# AC.net
KiCad netlist of a schematic drawn in EAGLE
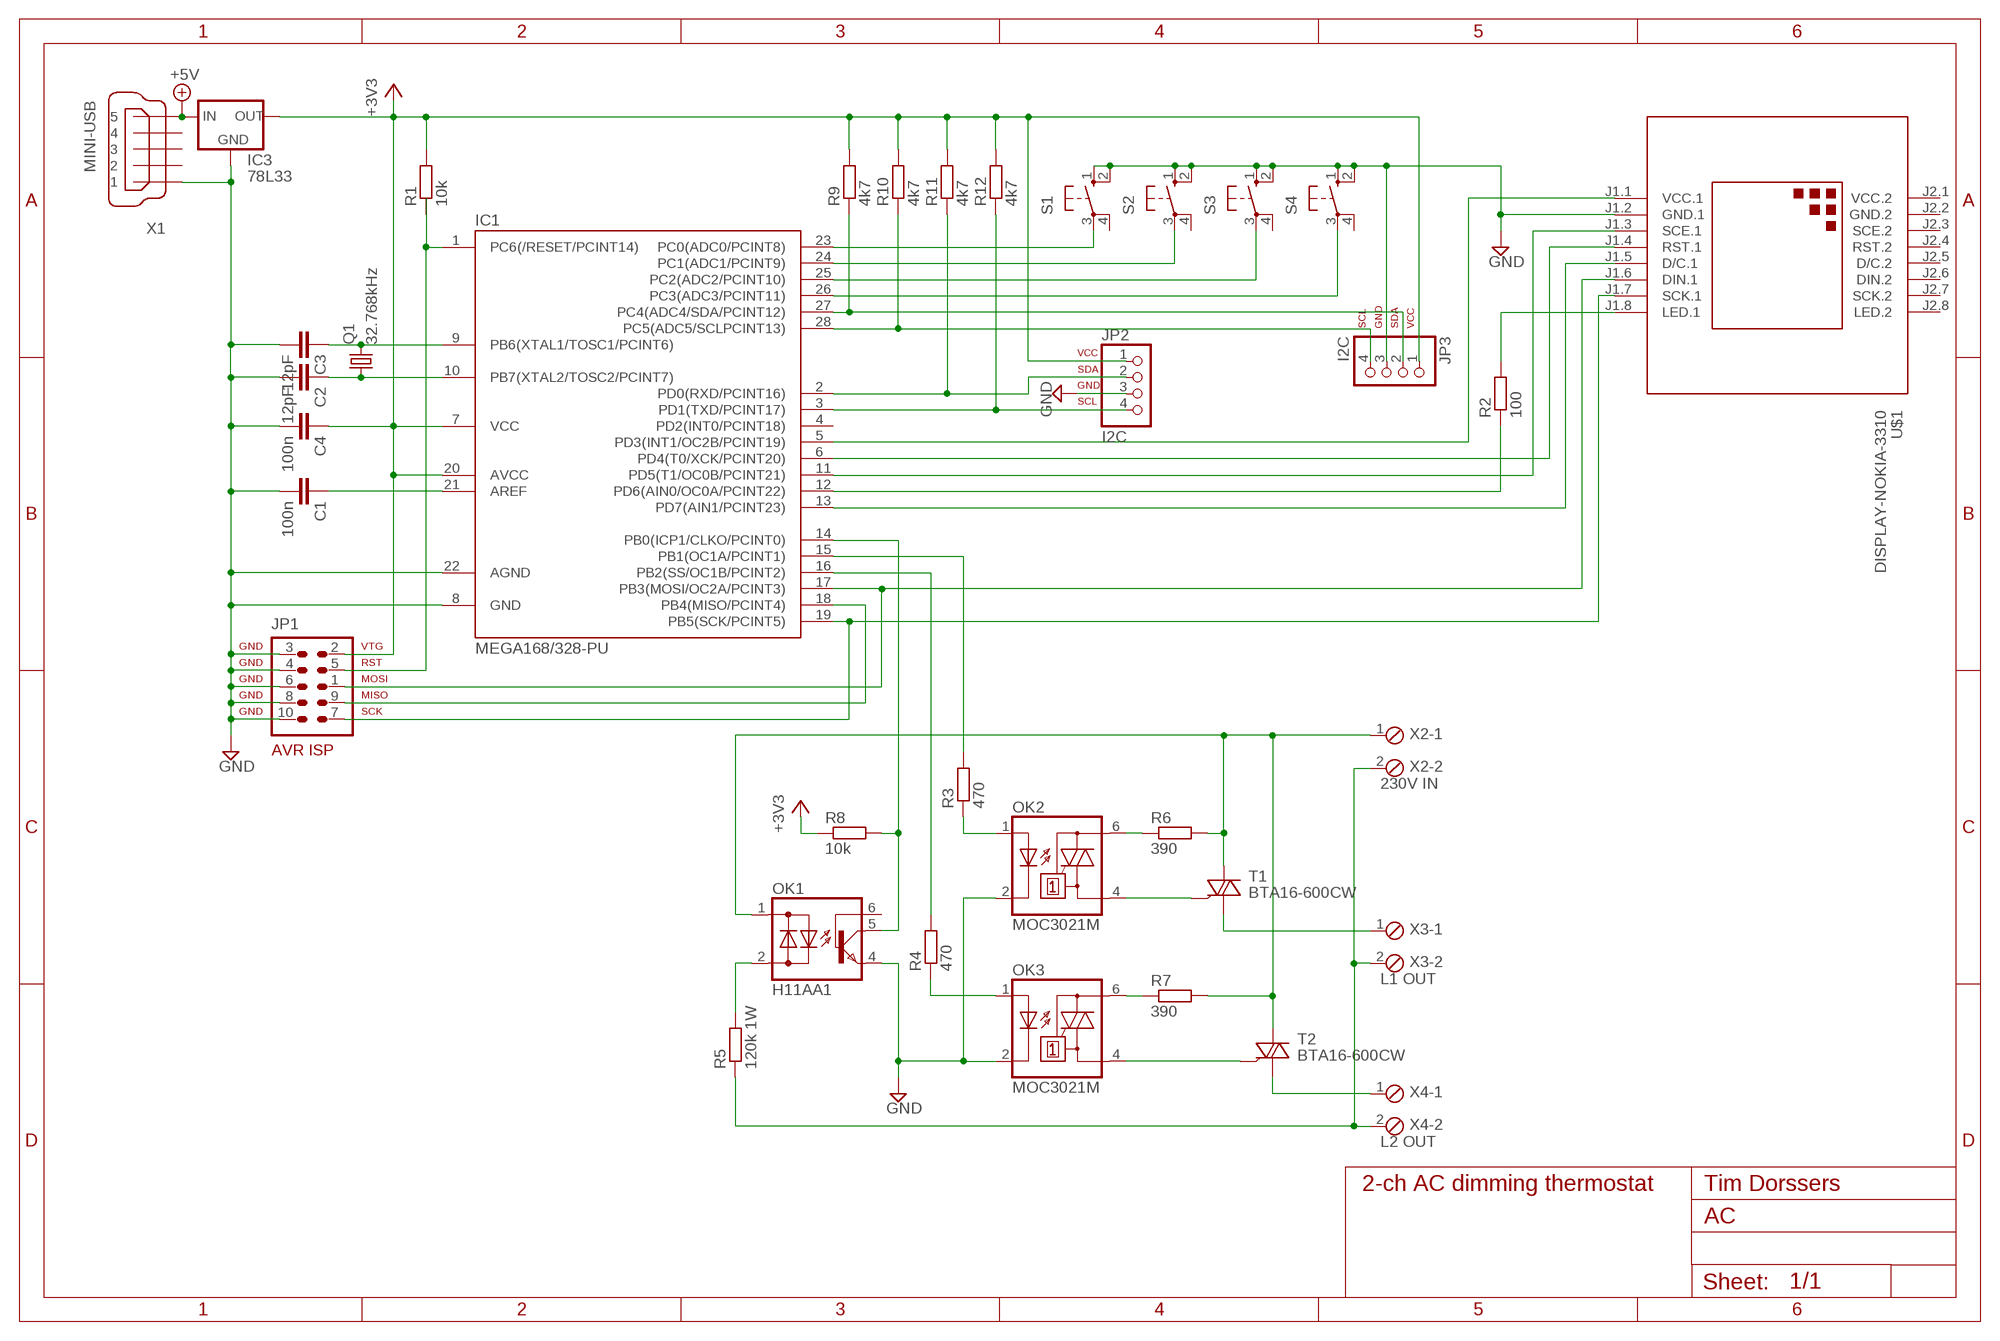
[diagram p0: schematic, sheet 1]

(export (version "E")
  (design (tool "Eeschema 10.0.6"))
  (components
    (comp (ref "C1")
      (value "100n")
      (footprint "eagle-import:C025-025X050")
      (libsource (lib "eagle-import") (part "C-EU025-025X050"))
    )
    (comp (ref "C2")
      (value "12pF")
      (footprint "eagle-import:C025-024X044")
      (libsource (lib "eagle-import") (part "C-EU025-024X044"))
    )
    (comp (ref "C3")
      (value "12pF")
      (footprint "eagle-import:C025-024X044")
      (libsource (lib "eagle-import") (part "C-EU025-024X044"))
    )
    (comp (ref "C4")
      (value "100n")
      (footprint "eagle-import:C025-025X050")
      (libsource (lib "eagle-import") (part "C-EU025-025X050"))
    )
    (comp (ref "IC1")
      (value "MEGA168/328-PU")
      (footprint "eagle-import:DIL28-3")
      (libsource (lib "eagle-import") (part "MEGA48/88/168-PU"))
    )
    (comp (ref "IC3")
      (value "78L33")
      (footprint "eagle-import:78LXX")
      (libsource (lib "eagle-import") (part "78LXX"))
    )
    (comp (ref "JP1")
      (value "AVR-ISP-10")
      (footprint "eagle-import:AVR-ISP-10")
      (libsource (lib "eagle-import") (part "AVR-ISP-10"))
    )
    (comp (ref "JP2")
      (value "I2C")
      (footprint "eagle-import:1X04")
      (libsource (lib "eagle-import") (part "PINHD-1X4"))
    )
    (comp (ref "JP3")
      (value "I2C")
      (footprint "eagle-import:1X04")
      (libsource (lib "eagle-import") (part "PINHD-1X4"))
    )
    (comp (ref "OK1")
      (value "H11AA1")
      (footprint "eagle-import:DIL06")
      (fields (field (name "MF") "VISHAY/TELEFUNKEN") (field (name "MPN") "IL250"))
      (libsource (lib "eagle-import") (part "IL250"))
    )
    (comp (ref "OK2")
      (value "MOC3021M")
      (footprint "eagle-import:DIL06")
      (fields (field (name "MF") "FAIRCHILD SEMICONDUCTOR") (field (name "MPN") "MOC3021-M"))
      (libsource (lib "eagle-import") (part "MOC30M21"))
    )
    (comp (ref "OK3")
      (value "MOC3021M")
      (footprint "eagle-import:DIL06")
      (fields (field (name "MF") "FAIRCHILD SEMICONDUCTOR") (field (name "MPN") "MOC3021-M"))
      (libsource (lib "eagle-import") (part "MOC30M21"))
    )
    (comp (ref "Q1")
      (value "32.768kHz")
      (footprint "eagle-import:HC49U-V")
      (libsource (lib "eagle-import") (part "CRYSTALHC49U-V"))
    )
    (comp (ref "R1")
      (value "10k")
      (footprint "eagle-import:0204_7")
      (libsource (lib "eagle-import") (part "R-EU_0204/7"))
    )
    (comp (ref "R2")
      (value "100")
      (footprint "eagle-import:0204_7")
      (libsource (lib "eagle-import") (part "R-EU_0204/7"))
    )
    (comp (ref "R3")
      (value "470")
      (footprint "eagle-import:0204_7")
      (libsource (lib "eagle-import") (part "R-EU_0204/7"))
    )
    (comp (ref "R4")
      (value "470")
      (footprint "eagle-import:0204_7")
      (libsource (lib "eagle-import") (part "R-EU_0204/7"))
    )
    (comp (ref "R5")
      (value "120k 1W")
      (footprint "eagle-import:0207_10")
      (libsource (lib "eagle-import") (part "R-EU_0207/10"))
    )
    (comp (ref "R6")
      (value "390")
      (footprint "eagle-import:0204_7")
      (libsource (lib "eagle-import") (part "R-EU_0204/7"))
    )
    (comp (ref "R7")
      (value "390")
      (footprint "eagle-import:0204_7")
      (libsource (lib "eagle-import") (part "R-EU_0204/7"))
    )
    (comp (ref "R8")
      (value "10k")
      (footprint "eagle-import:0207_10")
      (libsource (lib "eagle-import") (part "R-EU_0207/10"))
    )
    (comp (ref "R9")
      (value "4k7")
      (footprint "eagle-import:0204_7")
      (libsource (lib "eagle-import") (part "R-EU_0204/7"))
    )
    (comp (ref "R10")
      (value "4k7")
      (footprint "eagle-import:0204_7")
      (libsource (lib "eagle-import") (part "R-EU_0204/7"))
    )
    (comp (ref "R11")
      (value "4k7")
      (footprint "eagle-import:0204_7")
      (libsource (lib "eagle-import") (part "R-EU_0204/7"))
    )
    (comp (ref "R12")
      (value "4k7")
      (footprint "eagle-import:0204_7")
      (libsource (lib "eagle-import") (part "R-EU_0204/7"))
    )
    (comp (ref "S1")
      (value "10-XX")
      (footprint "eagle-import:B3F-10XX")
      (fields (field (name "MPN") "B3F-1000"))
      (libsource (lib "eagle-import") (part "10-XX"))
    )
    (comp (ref "S2")
      (value "10-XX")
      (footprint "eagle-import:B3F-10XX")
      (fields (field (name "MPN") "B3F-1000"))
      (libsource (lib "eagle-import") (part "10-XX"))
    )
    (comp (ref "S3")
      (value "10-XX")
      (footprint "eagle-import:B3F-10XX")
      (fields (field (name "MPN") "B3F-1000"))
      (libsource (lib "eagle-import") (part "10-XX"))
    )
    (comp (ref "S4")
      (value "10-XX")
      (footprint "eagle-import:B3F-10XX")
      (fields (field (name "MPN") "B3F-1000"))
      (libsource (lib "eagle-import") (part "10-XX"))
    )
    (comp (ref "T1")
      (value "BTA16-600CW")
      (footprint "eagle-import:TO220BV")
      (libsource (lib "eagle-import") (part "BT138-V"))
    )
    (comp (ref "T2")
      (value "BTA16-600CW")
      (footprint "eagle-import:TO220BV")
      (libsource (lib "eagle-import") (part "BT138-V"))
    )
    (comp (ref "U$1")
      (value "DISPLAY-NOKIA-3310")
      (footprint "eagle-import:DISPLAY-NOKIA-3310")
      (libsource (lib "eagle-import") (part "DISPLAY-NOKIA-3310"))
    )
    (comp (ref "X1")
      (value "MINI-USB")
      (footprint "eagle-import:32005-601")
      (libsource (lib "eagle-import") (part "MINI-USB_SHIELD5P2-32005-601"))
    )
    (comp (ref "X2")
      (value "230V IN")
      (footprint "eagle-import:2POL254")
      (libsource (lib "eagle-import") (part "MPT2"))
    )
    (comp (ref "X3")
      (value "L1 OUT")
      (footprint "eagle-import:2POL254")
      (libsource (lib "eagle-import") (part "MPT2"))
    )
    (comp (ref "X4")
      (value "L2 OUT")
      (footprint "eagle-import:2POL254")
      (libsource (lib "eagle-import") (part "MPT2"))
    )
  )
  (nets
    (net (code "1") (name "+3V3") (class "Default")
      (node (ref "C4") (pin "1") (pinfunction "1_1") (pintype "passive"))
      (node (ref "IC1") (pin "20") (pinfunction "AVCC_20") (pintype "passive"))
      (node (ref "IC1") (pin "7") (pinfunction "VCC_7") (pintype "power_in"))
      (node (ref "IC3") (pin "OUT") (pinfunction "OUT_OUT") (pintype "passive"))
      (node (ref "JP1") (pin "2") (pinfunction "2_2") (pintype "passive"))
      (node (ref "JP2") (pin "1") (pinfunction "1_1") (pintype "passive"))
      (node (ref "JP3") (pin "1") (pinfunction "1_1") (pintype "passive"))
      (node (ref "R1") (pin "2") (pinfunction "2_2") (pintype "passive"))
      (node (ref "R10") (pin "2") (pinfunction "2_2") (pintype "passive"))
      (node (ref "R11") (pin "2") (pinfunction "2_2") (pintype "passive"))
      (node (ref "R12") (pin "2") (pinfunction "2_2") (pintype "passive"))
      (node (ref "R8") (pin "1") (pinfunction "1_1") (pintype "passive"))
      (node (ref "R9") (pin "2") (pinfunction "2_2") (pintype "passive"))
    )
    (net (code "2") (name "+5V") (class "Default")
      (node (ref "IC3") (pin "IN") (pinfunction "IN_IN") (pintype "input"))
      (node (ref "X1") (pin "5") (pinfunction "5_5") (pintype "passive"))
    )
    (net (code "3") (name "/GND.2") (class "Default")
      (node (ref "U$1") (pin "J2.2") (pinfunction "GND.2_J2.2") (pintype "power_in"))
    )
    (net (code "4") (name "/VCC.2") (class "Default")
      (node (ref "U$1") (pin "J2.1") (pinfunction "VCC.2_J2.1") (pintype "power_in"))
    )
    (net (code "5") (name "GND") (class "Default")
      (node (ref "C1") (pin "2") (pinfunction "2_2") (pintype "passive"))
      (node (ref "C2") (pin "2") (pinfunction "2_2") (pintype "passive"))
      (node (ref "C3") (pin "2") (pinfunction "2_2") (pintype "passive"))
      (node (ref "C4") (pin "2") (pinfunction "2_2") (pintype "passive"))
      (node (ref "IC1") (pin "22") (pinfunction "AGND_22") (pintype "power_in"))
      (node (ref "IC1") (pin "8") (pinfunction "GND_8") (pintype "power_in"))
      (node (ref "IC3") (pin "GND") (pinfunction "GND_GND") (pintype "input"))
      (node (ref "JP1") (pin "10") (pinfunction "10_10") (pintype "passive"))
      (node (ref "JP1") (pin "3") (pinfunction "3_3") (pintype "passive"))
      (node (ref "JP1") (pin "4") (pinfunction "4_4") (pintype "passive"))
      (node (ref "JP1") (pin "6") (pinfunction "6_6") (pintype "passive"))
      (node (ref "JP1") (pin "8") (pinfunction "8_8") (pintype "passive"))
      (node (ref "JP2") (pin "3") (pinfunction "3_3") (pintype "passive"))
      (node (ref "JP3") (pin "3") (pinfunction "3_3") (pintype "passive"))
      (node (ref "OK1") (pin "4") (pinfunction "E_4") (pintype "passive"))
      (node (ref "OK2") (pin "2") (pinfunction "C_2") (pintype "passive"))
      (node (ref "OK3") (pin "2") (pinfunction "C_2") (pintype "passive"))
      (node (ref "S1") (pin "1") (pinfunction "S_1") (pintype "passive"))
      (node (ref "S1") (pin "2") (pinfunction "S1_2") (pintype "passive"))
      (node (ref "S2") (pin "1") (pinfunction "S_1") (pintype "passive"))
      (node (ref "S2") (pin "2") (pinfunction "S1_2") (pintype "passive"))
      (node (ref "S3") (pin "1") (pinfunction "S_1") (pintype "passive"))
      (node (ref "S3") (pin "2") (pinfunction "S1_2") (pintype "passive"))
      (node (ref "S4") (pin "1") (pinfunction "S_1") (pintype "passive"))
      (node (ref "S4") (pin "2") (pinfunction "S1_2") (pintype "passive"))
      (node (ref "U$1") (pin "J1.2") (pinfunction "GND.1_J1.2") (pintype "power_in"))
      (node (ref "X1") (pin "1") (pinfunction "1_1") (pintype "passive"))
    )
    (net (code "6") (name "Net-(IC1-AREF)") (class "Default")
      (node (ref "C1") (pin "1") (pinfunction "1_1") (pintype "passive"))
      (node (ref "IC1") (pin "21") (pinfunction "AREF_21") (pintype "passive"))
    )
    (net (code "7") (name "Net-(IC1-PB0(ICP1{slash}CLKO{slash}PCINT0))") (class "Default")
      (node (ref "IC1") (pin "14") (pinfunction "PB0(ICP1/CLKO/PCINT0)_14") (pintype "bidirectional"))
      (node (ref "OK1") (pin "5") (pinfunction "C_5") (pintype "passive"))
      (node (ref "R8") (pin "2") (pinfunction "2_2") (pintype "passive"))
    )
    (net (code "8") (name "Net-(IC1-PB1(OC1A{slash}PCINT1))") (class "Default")
      (node (ref "IC1") (pin "15") (pinfunction "PB1(OC1A/PCINT1)_15") (pintype "bidirectional"))
      (node (ref "R3") (pin "2") (pinfunction "2_2") (pintype "passive"))
    )
    (net (code "9") (name "Net-(IC1-PB2(SS{slash}OC1B{slash}PCINT2))") (class "Default")
      (node (ref "IC1") (pin "16") (pinfunction "PB2(SS/OC1B/PCINT2)_16") (pintype "bidirectional"))
      (node (ref "R4") (pin "2") (pinfunction "2_2") (pintype "passive"))
    )
    (net (code "10") (name "Net-(IC1-PB3(MOSI{slash}OC2A{slash}PCINT3))") (class "Default")
      (node (ref "IC1") (pin "17") (pinfunction "PB3(MOSI/OC2A/PCINT3)_17") (pintype "bidirectional"))
      (node (ref "JP1") (pin "1") (pinfunction "1_1") (pintype "passive"))
      (node (ref "U$1") (pin "J1.6") (pinfunction "DIN.1_J1.6") (pintype "bidirectional"))
    )
    (net (code "11") (name "Net-(IC1-PB4(MISO{slash}PCINT4))") (class "Default")
      (node (ref "IC1") (pin "18") (pinfunction "PB4(MISO/PCINT4)_18") (pintype "bidirectional"))
      (node (ref "JP1") (pin "9") (pinfunction "9_9") (pintype "passive"))
    )
    (net (code "12") (name "Net-(IC1-PB5(SCK{slash}PCINT5))") (class "Default")
      (node (ref "IC1") (pin "19") (pinfunction "PB5(SCK/PCINT5)_19") (pintype "bidirectional"))
      (node (ref "JP1") (pin "7") (pinfunction "7_7") (pintype "passive"))
      (node (ref "U$1") (pin "J1.7") (pinfunction "SCK.1_J1.7") (pintype "bidirectional"))
    )
    (net (code "13") (name "Net-(IC1-PB6(XTAL1{slash}TOSC1{slash}PCINT6))") (class "Default")
      (node (ref "C3") (pin "1") (pinfunction "1_1") (pintype "passive"))
      (node (ref "IC1") (pin "9") (pinfunction "PB6(XTAL1/TOSC1/PCINT6)_9") (pintype "bidirectional"))
      (node (ref "Q1") (pin "2") (pinfunction "2_2") (pintype "passive"))
    )
    (net (code "14") (name "Net-(IC1-PB7(XTAL2{slash}TOSC2{slash}PCINT7))") (class "Default")
      (node (ref "C2") (pin "1") (pinfunction "1_1") (pintype "passive"))
      (node (ref "IC1") (pin "10") (pinfunction "PB7(XTAL2/TOSC2/PCINT7)_10") (pintype "bidirectional"))
      (node (ref "Q1") (pin "1") (pinfunction "1_1") (pintype "passive"))
    )
    (net (code "15") (name "Net-(IC1-PC0(ADC0{slash}PCINT8))") (class "Default")
      (node (ref "IC1") (pin "23") (pinfunction "PC0(ADC0/PCINT8)_23") (pintype "bidirectional"))
      (node (ref "S1") (pin "3") (pinfunction "P_3") (pintype "passive"))
    )
    (net (code "16") (name "Net-(IC1-PC1(ADC1{slash}PCINT9))") (class "Default")
      (node (ref "IC1") (pin "24") (pinfunction "PC1(ADC1/PCINT9)_24") (pintype "bidirectional"))
      (node (ref "S2") (pin "3") (pinfunction "P_3") (pintype "passive"))
    )
    (net (code "17") (name "Net-(IC1-PC2(ADC2{slash}PCINT10))") (class "Default")
      (node (ref "IC1") (pin "25") (pinfunction "PC2(ADC2/PCINT10)_25") (pintype "bidirectional"))
      (node (ref "S3") (pin "3") (pinfunction "P_3") (pintype "passive"))
    )
    (net (code "18") (name "Net-(IC1-PC3(ADC3{slash}PCINT11))") (class "Default")
      (node (ref "IC1") (pin "26") (pinfunction "PC3(ADC3/PCINT11)_26") (pintype "bidirectional"))
      (node (ref "S4") (pin "3") (pinfunction "P_3") (pintype "passive"))
    )
    (net (code "19") (name "Net-(IC1-PC4(ADC4{slash}SDA{slash}PCINT12))") (class "Default")
      (node (ref "IC1") (pin "27") (pinfunction "PC4(ADC4/SDA/PCINT12)_27") (pintype "bidirectional"))
      (node (ref "JP3") (pin "2") (pinfunction "2_2") (pintype "passive"))
      (node (ref "R9") (pin "1") (pinfunction "1_1") (pintype "passive"))
    )
    (net (code "20") (name "Net-(IC1-PC5(ADC5{slash}SCLPCINT13))") (class "Default")
      (node (ref "IC1") (pin "28") (pinfunction "PC5(ADC5/SCLPCINT13)_28") (pintype "bidirectional"))
      (node (ref "JP3") (pin "4") (pinfunction "4_4") (pintype "passive"))
      (node (ref "R10") (pin "1") (pinfunction "1_1") (pintype "passive"))
    )
    (net (code "21") (name "Net-(IC1-PC6({slash}RESET{slash}PCINT14))") (class "Default")
      (node (ref "IC1") (pin "1") (pinfunction "PC6(/RESET/PCINT14)_1") (pintype "bidirectional"))
      (node (ref "JP1") (pin "5") (pinfunction "5_5") (pintype "passive"))
      (node (ref "R1") (pin "1") (pinfunction "1_1") (pintype "passive"))
    )
    (net (code "22") (name "Net-(IC1-PD0(RXD{slash}PCINT16))") (class "Default")
      (node (ref "IC1") (pin "2") (pinfunction "PD0(RXD/PCINT16)_2") (pintype "bidirectional"))
      (node (ref "JP2") (pin "2") (pinfunction "2_2") (pintype "passive"))
      (node (ref "R11") (pin "1") (pinfunction "1_1") (pintype "passive"))
    )
    (net (code "23") (name "Net-(IC1-PD1(TXD{slash}PCINT17))") (class "Default")
      (node (ref "IC1") (pin "3") (pinfunction "PD1(TXD/PCINT17)_3") (pintype "bidirectional"))
      (node (ref "JP2") (pin "4") (pinfunction "4_4") (pintype "passive"))
      (node (ref "R12") (pin "1") (pinfunction "1_1") (pintype "passive"))
    )
    (net (code "24") (name "Net-(IC1-PD3(INT1{slash}OC2B{slash}PCINT19))") (class "Default")
      (node (ref "IC1") (pin "5") (pinfunction "PD3(INT1/OC2B/PCINT19)_5") (pintype "bidirectional"))
      (node (ref "U$1") (pin "J1.1") (pinfunction "VCC.1_J1.1") (pintype "power_in"))
    )
    (net (code "25") (name "Net-(IC1-PD4(T0{slash}XCK{slash}PCINT20))") (class "Default")
      (node (ref "IC1") (pin "6") (pinfunction "PD4(T0/XCK/PCINT20)_6") (pintype "bidirectional"))
      (node (ref "U$1") (pin "J1.4") (pinfunction "RST.1_J1.4") (pintype "bidirectional"))
    )
    (net (code "26") (name "Net-(IC1-PD5(T1{slash}OC0B{slash}PCINT21))") (class "Default")
      (node (ref "IC1") (pin "11") (pinfunction "PD5(T1/OC0B/PCINT21)_11") (pintype "bidirectional"))
      (node (ref "U$1") (pin "J1.3") (pinfunction "SCE.1_J1.3") (pintype "bidirectional"))
    )
    (net (code "27") (name "Net-(IC1-PD6(AIN0{slash}OC0A{slash}PCINT22))") (class "Default")
      (node (ref "IC1") (pin "12") (pinfunction "PD6(AIN0/OC0A/PCINT22)_12") (pintype "bidirectional"))
      (node (ref "R2") (pin "1") (pinfunction "1_1") (pintype "passive"))
    )
    (net (code "28") (name "Net-(IC1-PD7(AIN1{slash}PCINT23))") (class "Default")
      (node (ref "IC1") (pin "13") (pinfunction "PD7(AIN1/PCINT23)_13") (pintype "bidirectional"))
      (node (ref "U$1") (pin "J1.5") (pinfunction "D/C.1_J1.5") (pintype "bidirectional"))
    )
    (net (code "29") (name "Net-(OK1-AC1)") (class "Default")
      (node (ref "OK1") (pin "1") (pinfunction "AC1_1") (pintype "passive"))
      (node (ref "R6") (pin "2") (pinfunction "2_2") (pintype "passive"))
      (node (ref "R7") (pin "2") (pinfunction "2_2") (pintype "passive"))
      (node (ref "T1") (pin "T2") (pinfunction "A2_T2") (pintype "passive"))
      (node (ref "T2") (pin "T2") (pinfunction "A2_T2") (pintype "passive"))
      (node (ref "X2") (pin "1") (pinfunction "1_1") (pintype "passive"))
    )
    (net (code "30") (name "Net-(OK1-AC2)") (class "Default")
      (node (ref "OK1") (pin "2") (pinfunction "AC2_2") (pintype "passive"))
      (node (ref "R5") (pin "2") (pinfunction "2_2") (pintype "passive"))
    )
    (net (code "31") (name "Net-(OK2-A)") (class "Default")
      (node (ref "OK2") (pin "1") (pinfunction "A_1") (pintype "passive"))
      (node (ref "R3") (pin "1") (pinfunction "1_1") (pintype "passive"))
    )
    (net (code "32") (name "Net-(OK2-A1)") (class "Default")
      (node (ref "OK2") (pin "4") (pinfunction "A1_4") (pintype "passive"))
      (node (ref "T1") (pin "G") (pinfunction "G_G") (pintype "passive"))
    )
    (net (code "33") (name "Net-(OK2-A2)") (class "Default")
      (node (ref "OK2") (pin "6") (pinfunction "A2_6") (pintype "passive"))
      (node (ref "R6") (pin "1") (pinfunction "1_1") (pintype "passive"))
    )
    (net (code "34") (name "Net-(OK3-A)") (class "Default")
      (node (ref "OK3") (pin "1") (pinfunction "A_1") (pintype "passive"))
      (node (ref "R4") (pin "1") (pinfunction "1_1") (pintype "passive"))
    )
    (net (code "35") (name "Net-(OK3-A1)") (class "Default")
      (node (ref "OK3") (pin "4") (pinfunction "A1_4") (pintype "passive"))
      (node (ref "T2") (pin "G") (pinfunction "G_G") (pintype "passive"))
    )
    (net (code "36") (name "Net-(OK3-A2)") (class "Default")
      (node (ref "OK3") (pin "6") (pinfunction "A2_6") (pintype "passive"))
      (node (ref "R7") (pin "1") (pinfunction "1_1") (pintype "passive"))
    )
    (net (code "37") (name "Net-(T1-A1)") (class "Default")
      (node (ref "T1") (pin "T1") (pinfunction "A1_T1") (pintype "passive"))
      (node (ref "X3") (pin "1") (pinfunction "1_1") (pintype "passive"))
    )
    (net (code "38") (name "Net-(T2-A1)") (class "Default")
      (node (ref "T2") (pin "T1") (pinfunction "A1_T1") (pintype "passive"))
      (node (ref "X4") (pin "1") (pinfunction "1_1") (pintype "passive"))
    )
    (net (code "39") (name "Net-(U$1-LED.1)") (class "Default")
      (node (ref "R2") (pin "2") (pinfunction "2_2") (pintype "passive"))
      (node (ref "U$1") (pin "J1.8") (pinfunction "LED.1_J1.8") (pintype "input"))
    )
    (net (code "40") (name "Net-(X2B-1)") (class "Default")
      (node (ref "R5") (pin "1") (pinfunction "1_1") (pintype "passive"))
      (node (ref "X2") (pin "2") (pinfunction "1_2") (pintype "passive"))
      (node (ref "X3") (pin "2") (pinfunction "1_2") (pintype "passive"))
      (node (ref "X4") (pin "2") (pinfunction "1_2") (pintype "passive"))
    )
    (net (code "41") (name "unconnected-(IC1-PD2(INT0{slash}PCINT18)-Pad4)") (class "Default")
      (node (ref "IC1") (pin "4") (pinfunction "PD2(INT0/PCINT18)_4") (pintype "bidirectional"))
    )
    (net (code "42") (name "unconnected-(OK1-B-Pad6)") (class "Default")
      (node (ref "OK1") (pin "6") (pinfunction "B_6") (pintype "passive"))
    )
    (net (code "43") (name "unconnected-(S1-P1-Pad4)") (class "Default")
      (node (ref "S1") (pin "4") (pinfunction "P1_4") (pintype "passive"))
    )
    (net (code "44") (name "unconnected-(S2-P1-Pad4)") (class "Default")
      (node (ref "S2") (pin "4") (pinfunction "P1_4") (pintype "passive"))
    )
    (net (code "45") (name "unconnected-(S3-P1-Pad4)") (class "Default")
      (node (ref "S3") (pin "4") (pinfunction "P1_4") (pintype "passive"))
    )
    (net (code "46") (name "unconnected-(S4-P1-Pad4)") (class "Default")
      (node (ref "S4") (pin "4") (pinfunction "P1_4") (pintype "passive"))
    )
    (net (code "47") (name "unconnected-(U$1-DIN.2-PadJ2.6)") (class "Default")
      (node (ref "U$1") (pin "J2.6") (pinfunction "DIN.2_J2.6") (pintype "bidirectional"))
    )
    (net (code "48") (name "unconnected-(U$1-D{slash}C.2-PadJ2.5)") (class "Default")
      (node (ref "U$1") (pin "J2.5") (pinfunction "D/C.2_J2.5") (pintype "bidirectional"))
    )
    (net (code "49") (name "unconnected-(U$1-LED.2-PadJ2.8)") (class "Default")
      (node (ref "U$1") (pin "J2.8") (pinfunction "LED.2_J2.8") (pintype "input"))
    )
    (net (code "50") (name "unconnected-(U$1-RST.2-PadJ2.4)") (class "Default")
      (node (ref "U$1") (pin "J2.4") (pinfunction "RST.2_J2.4") (pintype "bidirectional"))
    )
    (net (code "51") (name "unconnected-(U$1-SCE.2-PadJ2.3)") (class "Default")
      (node (ref "U$1") (pin "J2.3") (pinfunction "SCE.2_J2.3") (pintype "bidirectional"))
    )
    (net (code "52") (name "unconnected-(U$1-SCK.2-PadJ2.7)") (class "Default")
      (node (ref "U$1") (pin "J2.7") (pinfunction "SCK.2_J2.7") (pintype "bidirectional"))
    )
    (net (code "53") (name "unconnected-(X1-Pad2)") (class "Default")
      (node (ref "X1") (pin "2") (pinfunction "2_2") (pintype "passive"))
    )
    (net (code "54") (name "unconnected-(X1-Pad3)") (class "Default")
      (node (ref "X1") (pin "3") (pinfunction "3_3") (pintype "passive"))
    )
    (net (code "55") (name "unconnected-(X1-Pad4)") (class "Default")
      (node (ref "X1") (pin "4") (pinfunction "4_4") (pintype "passive"))
    )
  )
)
